# Main.net
KiCad netlist of a schematic drawn in Altium Designer
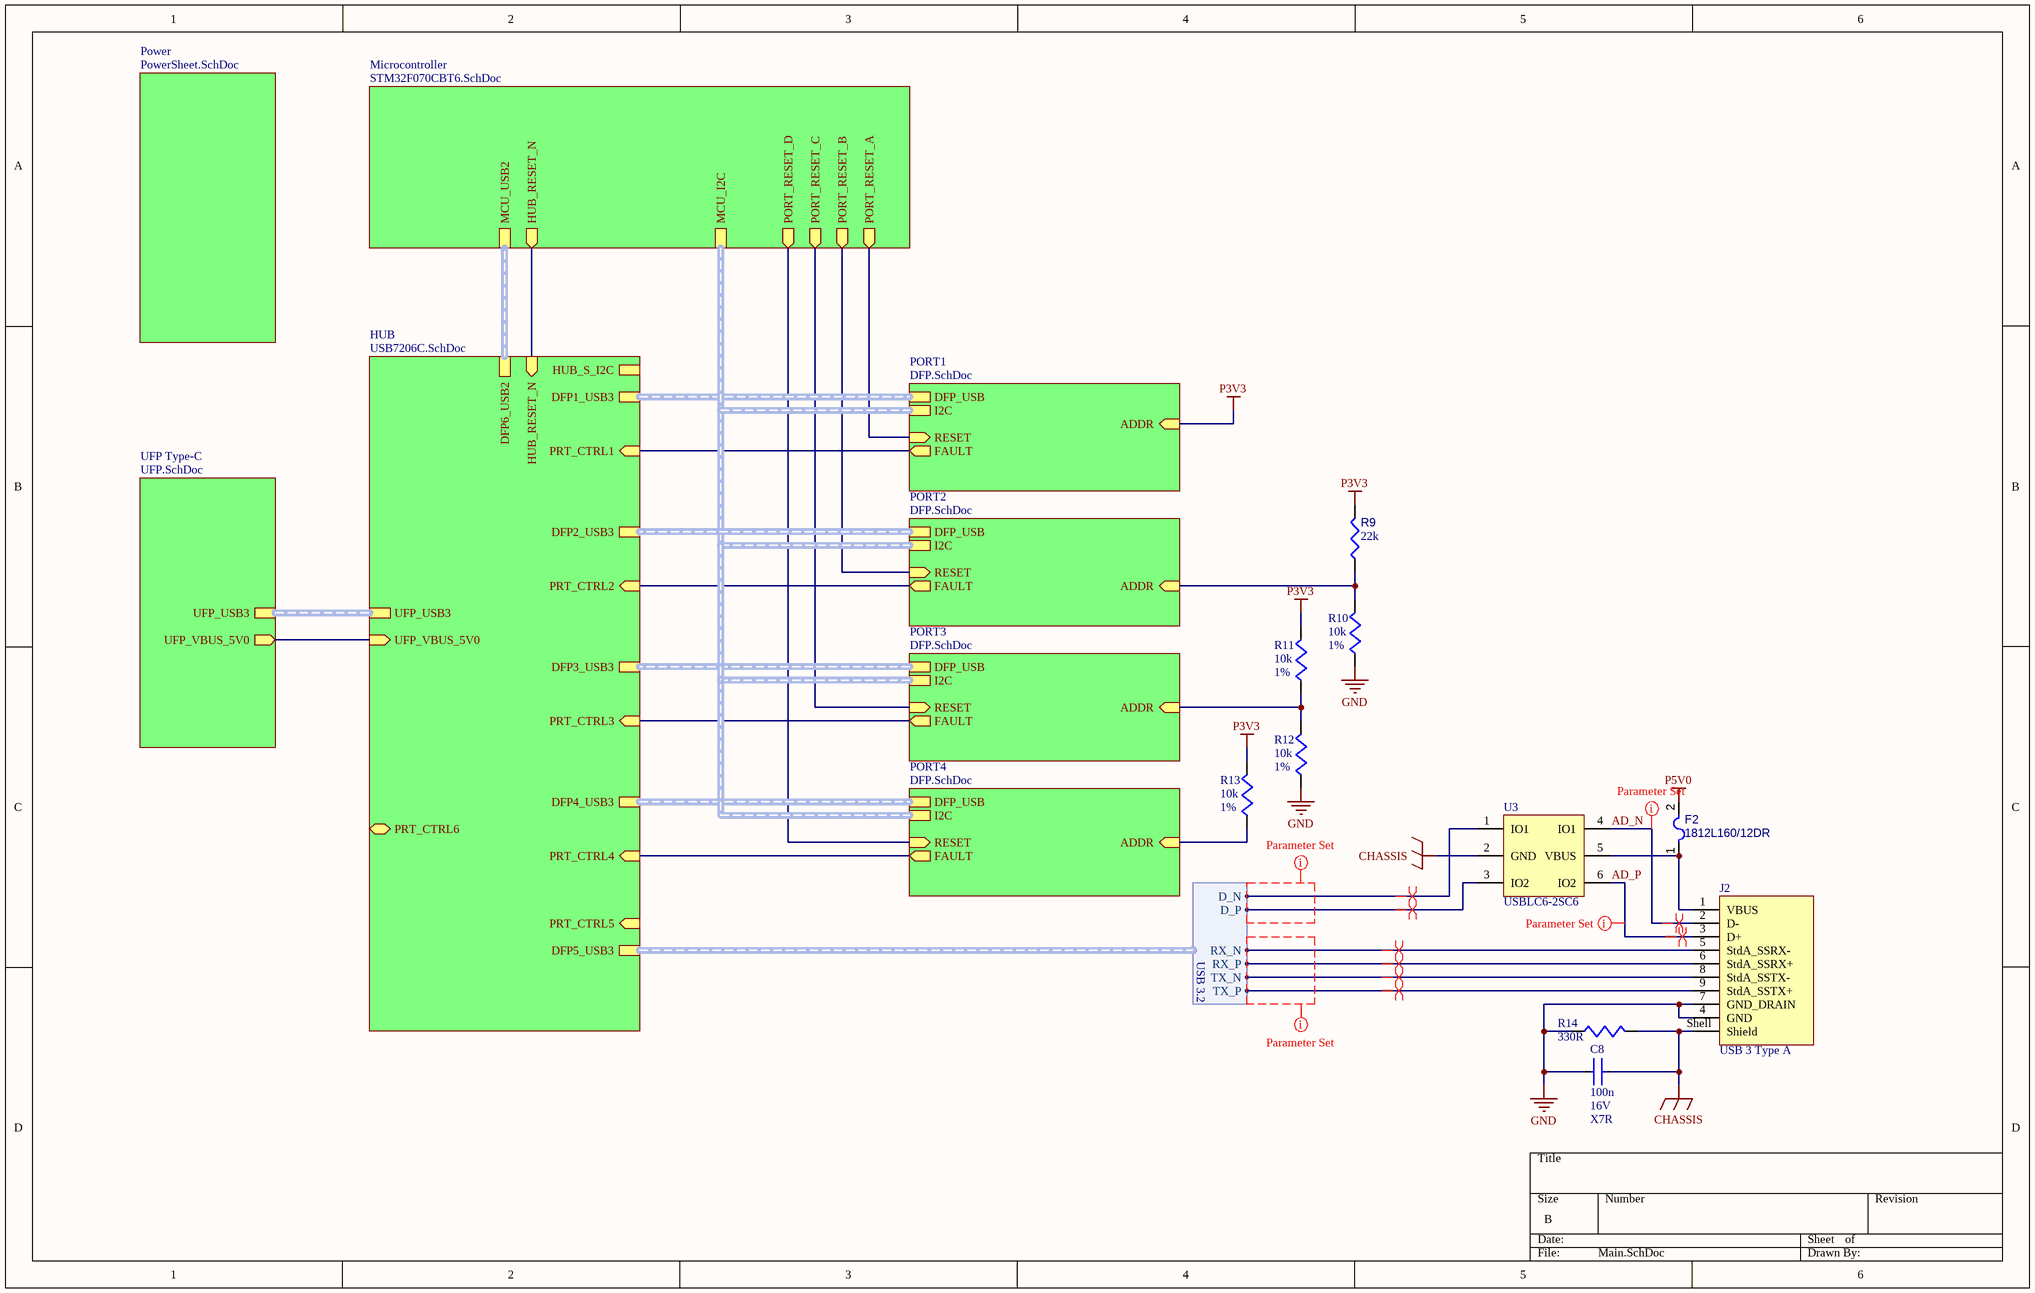
[diagram p0: Main.SchDoc]

(export (version "E")
  (design (tool "Eeschema 10.0.6"))
  (components
    (comp (ref "C8")
      (value "100n")
      (footprint "CAPC1005X06N")
      (description "16V 100nF X7R ±10% 0402 Multilayer Ceramic Capacitors MLCC - SMD/SMT ROHS")
      (fields
        (field (name "VOLTAGE") "16V")
        (field (name "DIELECTRIC") "X7R")
        (field (name "LCSC PART #") "C1525")
        (field (name "Comment") "100nF 16V 0402")
      )
      (libsource (lib "CWRU Motorsports") (part "Capacitor"))
    )
    (comp (ref "F2")
      (value "1812L160/12DR")
      (footprint "LFUS-1812L16012_V")
      (description "POLY-FUSE(R) Resettable PTC, 12 V, 1.6 A, -40 to 85 degC, 2-Pin SMD, RoHS, Tape and Reel")
      (fields (field (name "MANUFACTURER") "Littelfuse"))
      (libsource (lib "CWRU Motorsports") (part "FUSE-2"))
    )
    (comp (ref "J2")
      (value "USB 3 Type A")
      (footprint "692121030100")
      (description "USB Connector, 9 Contact(s), Female, Right Angle, Solder Terminal, Locking, Plug")
      (libsource (lib "CWRU Motorsports") (part "USB 3.0_Type A_Receptacle_1 Port"))
    )
    (comp (ref "R9")
      (value "22k")
      (footprint "RESC0402(1005)_L")
      (description "22K 0.063W 1% 0402 (1005 Metric)  SMD")
      (fields (field (name "POWER") "63mW") (field (name "TOLERANCE") "1%"))
      (libsource (lib "CWRU Motorsports") (part "22KR2F"))
    )
    (comp (ref "R10")
      (value "10k")
      (footprint "RESC1005X04M")
      (description "62.5mW Thick Film Resistors 50V ±100ppm/℃ ±1% 10kΩ 0402 Chip Resistor - Surface Mount ROHS")
      (fields
        (field (name "TOLERANCE") "1%")
        (field (name "LCSC PART #") "C60490")
        (field (name "Comment") "10k 1% 0402")
      )
      (libsource (lib "CWRU Motorsports") (part "Resistor"))
    )
    (comp (ref "R11")
      (value "10k")
      (footprint "RESC1005X04M")
      (description "62.5mW Thick Film Resistors 50V ±100ppm/℃ ±1% 10kΩ 0402 Chip Resistor - Surface Mount ROHS")
      (fields
        (field (name "TOLERANCE") "1%")
        (field (name "LCSC PART #") "C60490")
        (field (name "Comment") "10k 1% 0402")
      )
      (libsource (lib "CWRU Motorsports") (part "Resistor"))
    )
    (comp (ref "R12")
      (value "10k")
      (footprint "RESC1005X04M")
      (description "62.5mW Thick Film Resistors 50V ±100ppm/℃ ±1% 10kΩ 0402 Chip Resistor - Surface Mount ROHS")
      (fields
        (field (name "TOLERANCE") "1%")
        (field (name "LCSC PART #") "C60490")
        (field (name "Comment") "10k 1% 0402")
      )
      (libsource (lib "CWRU Motorsports") (part "Resistor"))
    )
    (comp (ref "R13")
      (value "10k")
      (footprint "RESC1005X04M")
      (description "62.5mW Thick Film Resistors 50V ±100ppm/℃ ±1% 10kΩ 0402 Chip Resistor - Surface Mount ROHS")
      (fields
        (field (name "TOLERANCE") "1%")
        (field (name "LCSC PART #") "C60490")
        (field (name "Comment") "10k 1% 0402")
      )
      (libsource (lib "CWRU Motorsports") (part "Resistor"))
    )
    (comp (ref "R14")
      (value "330R")
      (footprint "RESC1005X04M")
      (description "62.5mW Thick Film Resistors 50V ±100ppm/℃ ±1% 330Ω 0402 Chip Resistor - Surface Mount ROHS")
      (fields (field (name "TOLERANCE") "1%") (field (name "LCSC PART #") "C105875"))
      (libsource (lib "CWRU Motorsports") (part "Resistor"))
    )
    (comp (ref "U3")
      (value "USBLC6-2SC6")
      (footprint "SOT95P280X145-6N")
      (description "Trans Voltage Suppressor Diode, 5V V(RWM), Unidirectional, 1 Element, Silicon")
      (fields (field (name "LCSC PART #") "C7519"))
      (libsource (lib "CWRU Motorsports") (part "USBLC6-2SC6"))
    )
  )
  (nets
    (net (code "3") (name "/ADDR") (class "Default")
      (node (ref "R10") (pin "2") (pinfunction "2_2") (pintype "passive"))
      (node (ref "R9") (pin "1") (pinfunction "1_1") (pintype "passive"))
    )
    (net (code "4") (name "/ADDR_1") (class "Default")
      (node (ref "R13") (pin "1") (pinfunction "1_1") (pintype "passive"))
    )
    (net (code "5") (name "/ADDR_2") (class "Default")
      (node (ref "R11") (pin "1") (pinfunction "1_1") (pintype "passive"))
      (node (ref "R12") (pin "2") (pinfunction "2_2") (pintype "passive"))
    )
    (net (code "6") (name "/AD_N") (class "Default")
      (node (ref "J2") (pin "2") (pinfunction "D-_2") (pintype "passive"))
      (node (ref "U3") (pin "4") (pinfunction "IO1_4") (pintype "passive"))
    )
    (net (code "7") (name "/AD_P") (class "Default")
      (node (ref "J2") (pin "3") (pinfunction "D+_3") (pintype "passive"))
      (node (ref "U3") (pin "6") (pinfunction "IO2_6") (pintype "passive"))
    )
    (net (code "13") (name "/D_N") (class "Default")
      (node (ref "U3") (pin "1") (pinfunction "IO1_1") (pintype "passive"))
    )
    (net (code "14") (name "/D_P") (class "Default")
      (node (ref "U3") (pin "3") (pinfunction "IO2_3") (pintype "passive"))
    )
    (net (code "28") (name "/RX_N") (class "Default")
      (node (ref "J2") (pin "5") (pinfunction "StdA_SSRX-_5") (pintype "passive"))
    )
    (net (code "29") (name "/RX_P") (class "Default")
      (node (ref "J2") (pin "6") (pinfunction "StdA_SSRX+_6") (pintype "passive"))
    )
    (net (code "30") (name "/TX_N") (class "Default")
      (node (ref "J2") (pin "8") (pinfunction "StdA_SSTX-_8") (pintype "passive"))
    )
    (net (code "31") (name "/TX_P") (class "Default")
      (node (ref "J2") (pin "9") (pinfunction "StdA_SSTX+_9") (pintype "passive"))
    )
    (net (code "35") (name "CHASSIS") (class "Default")
      (node (ref "C8") (pin "1") (pinfunction "1_1") (pintype "passive"))
      (node (ref "J2") (pin "Shell") (pinfunction "Shield_Shell") (pintype "passive"))
      (node (ref "R14") (pin "2") (pinfunction "2_2") (pintype "passive"))
      (node (ref "U3") (pin "2") (pinfunction "GND_2") (pintype "passive"))
    )
    (net (code "36") (name "GND") (class "Default")
      (node (ref "C8") (pin "2") (pinfunction "2_2") (pintype "passive"))
      (node (ref "J2") (pin "4") (pinfunction "GND_4") (pintype "passive"))
      (node (ref "J2") (pin "7") (pinfunction "GND_DRAIN_7") (pintype "passive"))
      (node (ref "R10") (pin "1") (pinfunction "1_1") (pintype "passive"))
      (node (ref "R12") (pin "1") (pinfunction "1_1") (pintype "passive"))
      (node (ref "R14") (pin "1") (pinfunction "1_1") (pintype "passive"))
    )
    (net (code "37") (name "Net-(J2-VBUS)") (class "Default")
      (node (ref "F2") (pin "1") (pinfunction "1_1") (pintype "passive"))
      (node (ref "J2") (pin "1") (pinfunction "VBUS_1") (pintype "passive"))
      (node (ref "U3") (pin "5") (pinfunction "VBUS_5") (pintype "passive"))
    )
    (net (code "38") (name "P3V3") (class "Default")
      (node (ref "R11") (pin "2") (pinfunction "2_2") (pintype "passive"))
      (node (ref "R13") (pin "2") (pinfunction "2_2") (pintype "passive"))
      (node (ref "R9") (pin "2") (pinfunction "2_2") (pintype "passive"))
    )
    (net (code "39") (name "P5V0") (class "Default")
      (node (ref "F2") (pin "2") (pinfunction "2_2") (pintype "passive"))
    )
  )
)
